# MixerBF998.net
KiCad netlist of a schematic drawn in Altium Designer
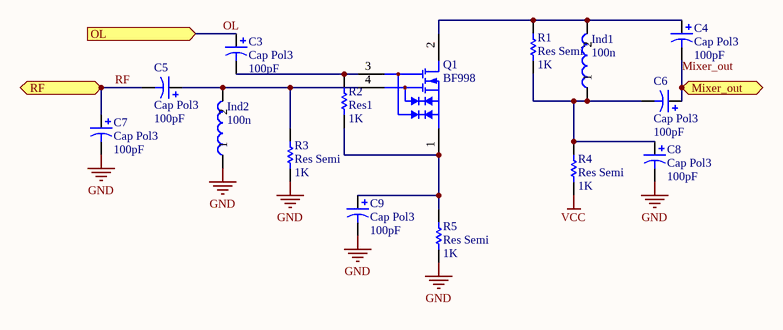
[diagram p0: MixerBF998.SchDoc]

(export (version "E")
  (design (tool "Eeschema 10.0.6"))
  (components
    (comp (ref "C3")
      (value "Cap Pol3")
      (footprint "C0805")
      (description "Polarized Capacitor (Surface Mount)")
      (fields (field (name "ALTIUM_VALUE") "100pF") (field (name "PUBLISHER") "Altium Limited"))
      (libsource (lib "Miscellaneous Devices") (part "Cap Pol3"))
    )
    (comp (ref "C4")
      (value "Cap Pol3")
      (footprint "C0805")
      (description "Polarized Capacitor (Surface Mount)")
      (fields (field (name "ALTIUM_VALUE") "100pF") (field (name "PUBLISHER") "Altium Limited"))
      (libsource (lib "Miscellaneous Devices") (part "Cap Pol3"))
    )
    (comp (ref "C5")
      (value "Cap Pol3")
      (footprint "C0805")
      (description "Polarized Capacitor (Surface Mount)")
      (fields (field (name "ALTIUM_VALUE") "100pF") (field (name "PUBLISHER") "Altium Limited"))
      (libsource (lib "Miscellaneous Devices") (part "Cap Pol3"))
    )
    (comp (ref "C6")
      (value "Cap Pol3")
      (footprint "C0805")
      (description "Polarized Capacitor (Surface Mount)")
      (fields (field (name "ALTIUM_VALUE") "100pF") (field (name "PUBLISHER") "Altium Limited"))
      (libsource (lib "Miscellaneous Devices") (part "Cap Pol3"))
    )
    (comp (ref "C7")
      (value "Cap Pol3")
      (footprint "C0805")
      (description "Polarized Capacitor (Surface Mount)")
      (fields (field (name "ALTIUM_VALUE") "100pF") (field (name "PUBLISHER") "Altium Limited"))
      (libsource (lib "Miscellaneous Devices") (part "Cap Pol3"))
    )
    (comp (ref "C8")
      (value "Cap Pol3")
      (footprint "C0805")
      (description "Polarized Capacitor (Surface Mount)")
      (fields (field (name "ALTIUM_VALUE") "100pF") (field (name "PUBLISHER") "Altium Limited"))
      (libsource (lib "Miscellaneous Devices") (part "Cap Pol3"))
    )
    (comp (ref "C9")
      (value "Cap Pol3")
      (footprint "C0805")
      (description "Polarized Capacitor (Surface Mount)")
      (fields (field (name "ALTIUM_VALUE") "100pF") (field (name "PUBLISHER") "Altium Limited"))
      (libsource (lib "Miscellaneous Devices") (part "Cap Pol3"))
    )
    (comp (ref "Ind1")
      (value "Ind2")
      (footprint "IND_7MM")
      (fields (field (name "VALOR") "100n"))
      (libsource (lib "epf") (part "Ind2"))
    )
    (comp (ref "Ind2")
      (value "Ind2")
      (footprint "Ind_4mm")
      (fields (field (name "VALOR") "100n"))
      (libsource (lib "epf") (part "Ind2"))
    )
    (comp (ref "Q1")
      (value "BF998")
      (footprint "SOT143_N")
      (description "Silicon N-channel Dual-gate MOSFET")
      (fields (field (name "PUBLISHER") "Altium Limited"))
      (libsource (lib "Philips Discrete MOSFET - Low Power") (part "BF998"))
    )
    (comp (ref "R1")
      (value "Res Semi")
      (footprint "2012[0805]")
      (description "Semiconductor Resistor")
      (fields (field (name "ALTIUM_VALUE") "1K") (field (name "PUBLISHER") "Altium Limited"))
      (libsource (lib "Miscellaneous Devices") (part "Res Semi"))
    )
    (comp (ref "R2")
      (value "Res1")
      (footprint "AXIAL-0.3")
      (description "Resistor")
      (fields (field (name "ALTIUM_VALUE") "1K") (field (name "PUBLISHER") "Altium Limited"))
      (libsource (lib "Miscellaneous Devices") (part "Res1"))
    )
    (comp (ref "R3")
      (value "Res Semi")
      (footprint "2012[0805]")
      (description "Semiconductor Resistor")
      (fields (field (name "ALTIUM_VALUE") "1K") (field (name "PUBLISHER") "Altium Limited"))
      (libsource (lib "Miscellaneous Devices") (part "Res Semi"))
    )
    (comp (ref "R4")
      (value "Res Semi")
      (footprint "2012[0805]")
      (description "Semiconductor Resistor")
      (fields (field (name "ALTIUM_VALUE") "1K") (field (name "PUBLISHER") "Altium Limited"))
      (libsource (lib "Miscellaneous Devices") (part "Res Semi"))
    )
    (comp (ref "R5")
      (value "Res Semi")
      (footprint "2012[0805]")
      (description "Semiconductor Resistor")
      (fields (field (name "ALTIUM_VALUE") "1K") (field (name "PUBLISHER") "Altium Limited"))
      (libsource (lib "Miscellaneous Devices") (part "Res Semi"))
    )
  )
  (nets
    (net (code "1") (name "/Mixer_out") (class "Default")
      (node (ref "C4") (pin "2") (pinfunction "2_2") (pintype "passive"))
      (node (ref "C6") (pin "1") (pinfunction "1_1") (pintype "passive"))
    )
    (net (code "2") (name "/OL") (class "Default")
      (node (ref "C3") (pin "1") (pinfunction "1_1") (pintype "passive"))
    )
    (net (code "3") (name "/RF") (class "Default")
      (node (ref "C5") (pin "2") (pinfunction "2_2") (pintype "passive"))
      (node (ref "C7") (pin "1") (pinfunction "1_1") (pintype "passive"))
    )
    (net (code "4") (name "GND") (class "Default")
      (node (ref "C7") (pin "2") (pinfunction "2_2") (pintype "passive"))
      (node (ref "C8") (pin "2") (pinfunction "2_2") (pintype "passive"))
      (node (ref "C9") (pin "2") (pinfunction "2_2") (pintype "passive"))
      (node (ref "Ind2") (pin "1") (pinfunction "1_1") (pintype "passive"))
      (node (ref "R3") (pin "1") (pinfunction "1_1") (pintype "passive"))
      (node (ref "R5") (pin "1") (pinfunction "1_1") (pintype "passive"))
    )
    (net (code "5") (name "Net-(C6-Pad2)") (class "Default")
      (node (ref "C6") (pin "2") (pinfunction "2_2") (pintype "passive"))
      (node (ref "C8") (pin "1") (pinfunction "1_1") (pintype "passive"))
      (node (ref "Ind1") (pin "1") (pinfunction "1_1") (pintype "passive"))
      (node (ref "R1") (pin "1") (pinfunction "1_1") (pintype "passive"))
      (node (ref "R4") (pin "2") (pinfunction "2_2") (pintype "passive"))
    )
    (net (code "6") (name "Net-(Q1-D)") (class "Default")
      (node (ref "C4") (pin "1") (pinfunction "1_1") (pintype "passive"))
      (node (ref "Ind1") (pin "2") (pinfunction "2_2") (pintype "passive"))
      (node (ref "Q1") (pin "2") (pinfunction "D_2") (pintype "passive"))
      (node (ref "R1") (pin "2") (pinfunction "2_2") (pintype "passive"))
    )
    (net (code "7") (name "Net-(Q1-G1)") (class "Default")
      (node (ref "C5") (pin "1") (pinfunction "1_1") (pintype "passive"))
      (node (ref "Ind2") (pin "2") (pinfunction "2_2") (pintype "passive"))
      (node (ref "Q1") (pin "4") (pinfunction "G1_4") (pintype "passive"))
      (node (ref "R3") (pin "2") (pinfunction "2_2") (pintype "passive"))
    )
    (net (code "8") (name "Net-(Q1-G2)") (class "Default")
      (node (ref "C3") (pin "2") (pinfunction "2_2") (pintype "passive"))
      (node (ref "Q1") (pin "3") (pinfunction "G2_3") (pintype "passive"))
      (node (ref "R2") (pin "2") (pinfunction "2_2") (pintype "passive"))
    )
    (net (code "9") (name "Net-(Q1-S)") (class "Default")
      (node (ref "C9") (pin "1") (pinfunction "1_1") (pintype "passive"))
      (node (ref "Q1") (pin "1") (pinfunction "S_1") (pintype "passive"))
      (node (ref "R2") (pin "1") (pinfunction "1_1") (pintype "passive"))
      (node (ref "R5") (pin "2") (pinfunction "2_2") (pintype "passive"))
    )
    (net (code "10") (name "VCC") (class "Default")
      (node (ref "R4") (pin "1") (pinfunction "1_1") (pintype "passive"))
    )
  )
)
